# Bluetooth_Module_1R1.net
KiCad netlist of a schematic drawn in Altium Designer
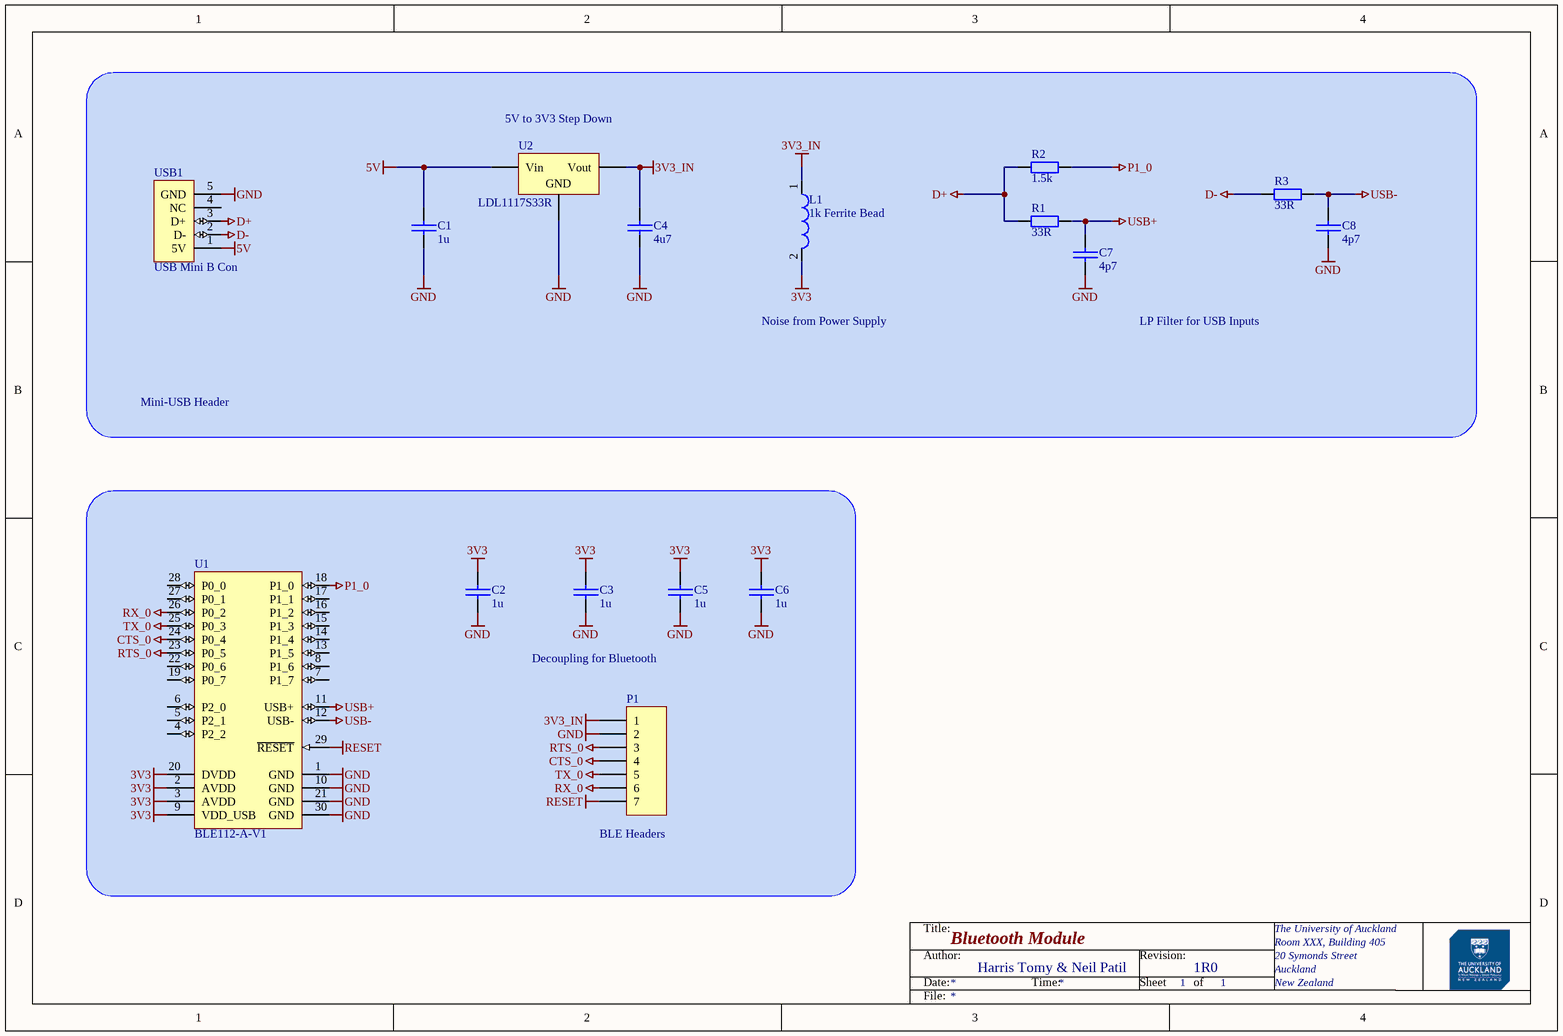
[diagram p0: Bluetooth_Module_1R1.SchDoc]

(export (version "E")
  (design (tool "Eeschema 10.0.6"))
  (components
    (comp (ref "C1")
      (value "1u")
      (footprint "C0805")
      (description "CCAP0805")
      (fields (field (name "MPN") "?"))
      (libsource (lib "E209_Lib") (part "CCAP0805"))
    )
    (comp (ref "C2")
      (value "1u")
      (footprint "C0805")
      (description "CCAP0805")
      (fields (field (name "MPN") "?"))
      (libsource (lib "E209_Lib") (part "CCAP0805"))
    )
    (comp (ref "C3")
      (value "1u")
      (footprint "C0805")
      (description "CCAP0805")
      (fields (field (name "MPN") "?"))
      (libsource (lib "E209_Lib") (part "CCAP0805"))
    )
    (comp (ref "C4")
      (value "4u7")
      (footprint "C1206")
      (description "CAP CER 0.1UF 100V C0G 1206")
      (fields (field (name "MPN") "C3216C0G2A104J160AC") (field (name "MANUFACTURER") "TDK Corporation"))
      (libsource (lib "E209_Lib") (part "Cap CER Decoup C3216C0G2A104J160AC"))
    )
    (comp (ref "C5")
      (value "1u")
      (footprint "C0805")
      (description "CCAP0805")
      (fields (field (name "MPN") "?"))
      (libsource (lib "E209_Lib") (part "CCAP0805"))
    )
    (comp (ref "C6")
      (value "1u")
      (footprint "C0805")
      (description "CCAP0805")
      (fields (field (name "MPN") "?"))
      (libsource (lib "E209_Lib") (part "CCAP0805"))
    )
    (comp (ref "C7")
      (value "4p7")
      (footprint "C0805")
      (description "CCAP0805")
      (fields (field (name "MPN") "?"))
      (libsource (lib "E209_Lib") (part "CCAP0805"))
    )
    (comp (ref "C8")
      (value "4p7")
      (footprint "C0805")
      (description "CCAP0805")
      (fields (field (name "MPN") "?"))
      (libsource (lib "E209_Lib") (part "CCAP0805"))
    )
    (comp (ref "L1")
      (value "1k Ferrite Bead")
      (footprint "SMD-1206")
      (description "SMD EMI Suppression Ferrite Bead WE-CBF, Z = 120 Ohm")
      (fields (field (name "PARTNUMBER") "742792113"))
      (libsource (lib "FE_Bead_1206") (part "742792113"))
    )
    (comp (ref "P1")
      (value "BLE Headers")
      (footprint "HDR1X7")
      (description "Header, 7-Pin")
      (fields (field (name "PUBLISHER") "Altium Limited"))
      (libsource (lib "Miscellaneous Connectors") (part "Header 7"))
    )
    (comp (ref "R1")
      (value "33R")
      (footprint "R0805")
      (description "RES0805")
      (fields (field (name "MPN") "?") (field (name "Comment") "Resistor 0805"))
      (libsource (lib "E209_Lib") (part "RES0805"))
    )
    (comp (ref "R2")
      (value "1.5k")
      (footprint "R0805")
      (description "RES0805")
      (fields (field (name "MPN") "?") (field (name "Comment") "Resistor 0805"))
      (libsource (lib "") (part "RES0805_1"))
    )
    (comp (ref "R3")
      (value "33R")
      (footprint "R0805")
      (description "RES0805")
      (fields (field (name "MPN") "?") (field (name "Comment") "Resistor 0805"))
      (libsource (lib "E209_Lib") (part "RES0805"))
    )
    (comp (ref "U1")
      (value "BLE112-A-V1")
      (footprint "BLUE-BLE112-A-V1_V")
      (libsource (lib "BLE112") (part "BLE112-A-V1"))
    )
    (comp (ref "U2")
      (value "LDL1117S33R")
      (footprint "SOT223L")
      (description "IC REG LINEAR 3.3V 1.2A SOT223")
      (fields (field (name "MANUFACTURER") "STMicroelectronics"))
      (libsource (lib "E209_Lib") (part "LDO LDL1117S33R"))
    )
    (comp (ref "USB1")
      (value "USB Mini B Con")
      (footprint "USB_UJ2MAB")
      (libsource (lib "CommonDevices_V1") (part "USBMiniB"))
    )
  )
  (nets
    (net (code "1") (name "3V3") (class "Default")
      (node (ref "C2") (pin "2") (pinfunction "2_2") (pintype "passive"))
      (node (ref "C3") (pin "2") (pinfunction "2_2") (pintype "passive"))
      (node (ref "C5") (pin "2") (pinfunction "2_2") (pintype "passive"))
      (node (ref "C6") (pin "2") (pinfunction "2_2") (pintype "passive"))
      (node (ref "L1") (pin "2") (pinfunction "2_2") (pintype "passive"))
      (node (ref "U1") (pin "2") (pinfunction "AVDD_2") (pintype "power_in"))
      (node (ref "U1") (pin "20") (pinfunction "DVDD_20") (pintype "power_in"))
      (node (ref "U1") (pin "3") (pinfunction "AVDD_3") (pintype "power_in"))
      (node (ref "U1") (pin "9") (pinfunction "VDD_USB_9") (pintype "power_in"))
    )
    (net (code "2") (name "3V3_IN") (class "Default")
      (node (ref "C4") (pin "2") (pinfunction "2_2") (pintype "passive"))
      (node (ref "L1") (pin "1") (pinfunction "1_1") (pintype "passive"))
      (node (ref "P1") (pin "1") (pinfunction "1_1") (pintype "passive"))
      (node (ref "U2") (pin "2") (pinfunction "Vout_2") (pintype "passive"))
    )
    (net (code "3") (name "5V") (class "Default")
      (node (ref "C1") (pin "2") (pinfunction "2_2") (pintype "passive"))
      (node (ref "U2") (pin "3") (pinfunction "Vin_3") (pintype "passive"))
      (node (ref "USB1") (pin "1") (pinfunction "5V_1") (pintype "passive"))
    )
    (net (code "4") (name "CTS_0") (class "Default")
      (node (ref "P1") (pin "4") (pinfunction "4_4") (pintype "passive"))
      (node (ref "U1") (pin "24") (pinfunction "P0_4_24") (pintype "bidirectional"))
    )
    (net (code "5") (name "D+") (class "Default")
      (node (ref "R1") (pin "2") (pinfunction "2_2") (pintype "passive"))
      (node (ref "R2") (pin "1") (pinfunction "1_1") (pintype "passive"))
      (node (ref "USB1") (pin "3") (pinfunction "D+_3") (pintype "bidirectional"))
    )
    (net (code "6") (name "D-") (class "Default")
      (node (ref "R3") (pin "2") (pinfunction "2_2") (pintype "passive"))
      (node (ref "USB1") (pin "2") (pinfunction "D-_2") (pintype "bidirectional"))
    )
    (net (code "7") (name "GND") (class "Default")
      (node (ref "C1") (pin "1") (pinfunction "1_1") (pintype "passive"))
      (node (ref "C2") (pin "1") (pinfunction "1_1") (pintype "passive"))
      (node (ref "C3") (pin "1") (pinfunction "1_1") (pintype "passive"))
      (node (ref "C4") (pin "1") (pinfunction "1_1") (pintype "passive"))
      (node (ref "C5") (pin "1") (pinfunction "1_1") (pintype "passive"))
      (node (ref "C6") (pin "1") (pinfunction "1_1") (pintype "passive"))
      (node (ref "C7") (pin "1") (pinfunction "1_1") (pintype "passive"))
      (node (ref "C8") (pin "1") (pinfunction "1_1") (pintype "passive"))
      (node (ref "P1") (pin "2") (pinfunction "2_2") (pintype "passive"))
      (node (ref "U1") (pin "1") (pinfunction "GND_1") (pintype "power_in"))
      (node (ref "U1") (pin "10") (pinfunction "GND_10") (pintype "power_in"))
      (node (ref "U1") (pin "21") (pinfunction "GND_21") (pintype "power_in"))
      (node (ref "U1") (pin "30") (pinfunction "GND_30") (pintype "power_in"))
      (node (ref "U2") (pin "1") (pinfunction "GND_1") (pintype "passive"))
      (node (ref "USB1") (pin "5") (pinfunction "GND_5") (pintype "passive"))
    )
    (net (code "8") (name "P1_0") (class "Default")
      (node (ref "R2") (pin "2") (pinfunction "2_2") (pintype "passive"))
      (node (ref "U1") (pin "18") (pinfunction "P1_0_18") (pintype "bidirectional"))
    )
    (net (code "9") (name "RESET") (class "Default")
      (node (ref "P1") (pin "7") (pinfunction "7_7") (pintype "passive"))
      (node (ref "U1") (pin "29") (pinfunction "~{RESET}_29") (pintype "input"))
    )
    (net (code "10") (name "RTS_0") (class "Default")
      (node (ref "P1") (pin "3") (pinfunction "3_3") (pintype "passive"))
      (node (ref "U1") (pin "23") (pinfunction "P0_5_23") (pintype "bidirectional"))
    )
    (net (code "11") (name "RX_0") (class "Default")
      (node (ref "P1") (pin "6") (pinfunction "6_6") (pintype "passive"))
      (node (ref "U1") (pin "26") (pinfunction "P0_2_26") (pintype "bidirectional"))
    )
    (net (code "12") (name "TX_0") (class "Default")
      (node (ref "P1") (pin "5") (pinfunction "5_5") (pintype "passive"))
      (node (ref "U1") (pin "25") (pinfunction "P0_3_25") (pintype "bidirectional"))
    )
    (net (code "13") (name "USB+") (class "Default")
      (node (ref "C7") (pin "2") (pinfunction "2_2") (pintype "passive"))
      (node (ref "R1") (pin "1") (pinfunction "1_1") (pintype "passive"))
      (node (ref "U1") (pin "11") (pinfunction "USB+_11") (pintype "bidirectional"))
    )
    (net (code "14") (name "USB-") (class "Default")
      (node (ref "C8") (pin "2") (pinfunction "2_2") (pintype "passive"))
      (node (ref "R3") (pin "1") (pinfunction "1_1") (pintype "passive"))
      (node (ref "U1") (pin "12") (pinfunction "USB-_12") (pintype "bidirectional"))
    )
    (net (code "15") (name "unconnected-(U1-P0_0-Pad28)") (class "Default")
      (node (ref "U1") (pin "28") (pinfunction "P0_0_28") (pintype "bidirectional"))
    )
    (net (code "16") (name "unconnected-(U1-P0_1-Pad27)") (class "Default")
      (node (ref "U1") (pin "27") (pinfunction "P0_1_27") (pintype "bidirectional"))
    )
    (net (code "17") (name "unconnected-(U1-P0_6-Pad22)") (class "Default")
      (node (ref "U1") (pin "22") (pinfunction "P0_6_22") (pintype "bidirectional"))
    )
    (net (code "18") (name "unconnected-(U1-P0_7-Pad19)") (class "Default")
      (node (ref "U1") (pin "19") (pinfunction "P0_7_19") (pintype "bidirectional"))
    )
    (net (code "19") (name "unconnected-(U1-P1_1-Pad17)") (class "Default")
      (node (ref "U1") (pin "17") (pinfunction "P1_1_17") (pintype "bidirectional"))
    )
    (net (code "20") (name "unconnected-(U1-P1_2-Pad16)") (class "Default")
      (node (ref "U1") (pin "16") (pinfunction "P1_2_16") (pintype "bidirectional"))
    )
    (net (code "21") (name "unconnected-(U1-P1_3-Pad15)") (class "Default")
      (node (ref "U1") (pin "15") (pinfunction "P1_3_15") (pintype "bidirectional"))
    )
    (net (code "22") (name "unconnected-(U1-P1_4-Pad14)") (class "Default")
      (node (ref "U1") (pin "14") (pinfunction "P1_4_14") (pintype "bidirectional"))
    )
    (net (code "23") (name "unconnected-(U1-P1_5-Pad13)") (class "Default")
      (node (ref "U1") (pin "13") (pinfunction "P1_5_13") (pintype "bidirectional"))
    )
    (net (code "24") (name "unconnected-(U1-P1_6-Pad8)") (class "Default")
      (node (ref "U1") (pin "8") (pinfunction "P1_6_8") (pintype "bidirectional"))
    )
    (net (code "25") (name "unconnected-(U1-P1_7-Pad7)") (class "Default")
      (node (ref "U1") (pin "7") (pinfunction "P1_7_7") (pintype "bidirectional"))
    )
    (net (code "26") (name "unconnected-(U1-P2_0-Pad6)") (class "Default")
      (node (ref "U1") (pin "6") (pinfunction "P2_0_6") (pintype "bidirectional"))
    )
    (net (code "27") (name "unconnected-(U1-P2_1-Pad5)") (class "Default")
      (node (ref "U1") (pin "5") (pinfunction "P2_1_5") (pintype "bidirectional"))
    )
    (net (code "28") (name "unconnected-(U1-P2_2-Pad4)") (class "Default")
      (node (ref "U1") (pin "4") (pinfunction "P2_2_4") (pintype "bidirectional"))
    )
    (net (code "29") (name "unconnected-(USB1-NC-Pad4)") (class "Default")
      (node (ref "USB1") (pin "4") (pinfunction "NC_4") (pintype "passive"))
    )
  )
)
